# guage.net
KiCad netlist of a schematic drawn in EAGLE
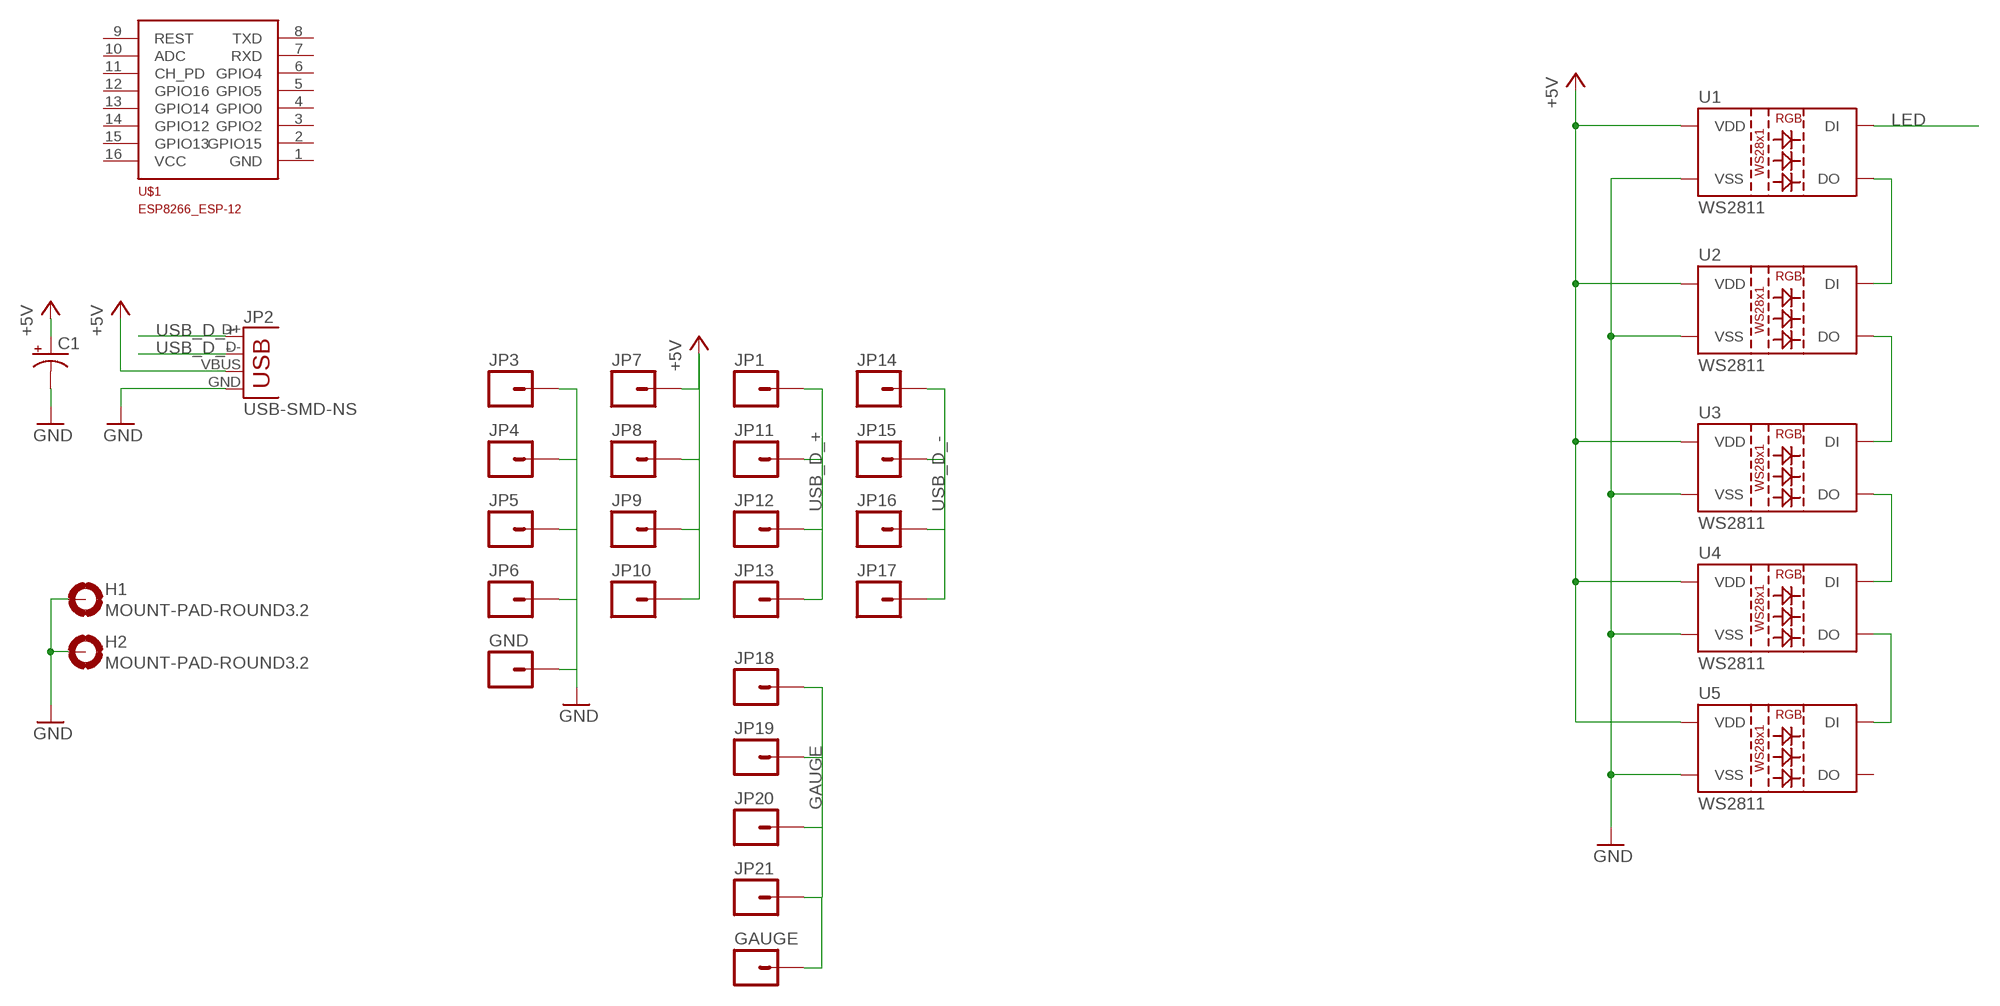
[diagram p0: schematic, sheet 1]

(export (version "E")
  (design (tool "Eeschema 10.0.6"))
  (components
    (comp (ref "C1")
      (value "100UF-25V-20%(PTH)")
      (footprint "eagle-import:CPOL-RADIAL-100UF-25V")
      (libsource (lib "eagle-import") (part "100UF-25V-20%(PTH)"))
    )
    (comp (ref "GAUGE")
      (value "M01OFFSET")
      (footprint "eagle-import:1X01_OFFSET")
      (libsource (lib "eagle-import") (part "M01OFFSET"))
    )
    (comp (ref "GND")
      (value "M01OFFSET")
      (footprint "eagle-import:1X01_OFFSET")
      (libsource (lib "eagle-import") (part "M01OFFSET"))
    )
    (comp (ref "H1")
      (value "MOUNT-PAD-ROUND3.2")
      (footprint "eagle-import:3,2-PAD")
      (libsource (lib "eagle-import") (part "MOUNT-PAD-ROUND3.2"))
    )
    (comp (ref "H2")
      (value "MOUNT-PAD-ROUND3.2")
      (footprint "eagle-import:3,2-PAD")
      (libsource (lib "eagle-import") (part "MOUNT-PAD-ROUND3.2"))
    )
    (comp (ref "JP1")
      (value "M01SMD-4.5X1.5")
      (footprint "eagle-import:PAD-1.5X4.5")
      (libsource (lib "eagle-import") (part "M01SMD-4.5X1.5"))
    )
    (comp (ref "JP2")
      (value "USB-SMD-NS")
      (footprint "eagle-import:USB-MINIB-NOSTOP")
      (libsource (lib "eagle-import") (part "USB-SMD-NS"))
    )
    (comp (ref "JP3")
      (value "M01SMD-4.5X1.5")
      (footprint "eagle-import:PAD-1.5X4.5")
      (libsource (lib "eagle-import") (part "M01SMD-4.5X1.5"))
    )
    (comp (ref "JP4")
      (value "M01SMD-4.5X1.5")
      (footprint "eagle-import:PAD-1.5X4.5")
      (libsource (lib "eagle-import") (part "M01SMD-4.5X1.5"))
    )
    (comp (ref "JP5")
      (value "M01SMD-4.5X1.5")
      (footprint "eagle-import:PAD-1.5X4.5")
      (libsource (lib "eagle-import") (part "M01SMD-4.5X1.5"))
    )
    (comp (ref "JP6")
      (value "M01SMD-4.5X1.5")
      (footprint "eagle-import:PAD-1.5X4.5")
      (libsource (lib "eagle-import") (part "M01SMD-4.5X1.5"))
    )
    (comp (ref "JP7")
      (value "M01SMD-4.5X1.5")
      (footprint "eagle-import:PAD-1.5X4.5")
      (libsource (lib "eagle-import") (part "M01SMD-4.5X1.5"))
    )
    (comp (ref "JP8")
      (value "M01SMD-4.5X1.5")
      (footprint "eagle-import:PAD-1.5X4.5")
      (libsource (lib "eagle-import") (part "M01SMD-4.5X1.5"))
    )
    (comp (ref "JP9")
      (value "M01SMD-4.5X1.5")
      (footprint "eagle-import:PAD-1.5X4.5")
      (libsource (lib "eagle-import") (part "M01SMD-4.5X1.5"))
    )
    (comp (ref "JP10")
      (value "M01SMD-4.5X1.5")
      (footprint "eagle-import:PAD-1.5X4.5")
      (libsource (lib "eagle-import") (part "M01SMD-4.5X1.5"))
    )
    (comp (ref "JP11")
      (value "M01SMD-4.5X1.5")
      (footprint "eagle-import:PAD-1.5X4.5")
      (libsource (lib "eagle-import") (part "M01SMD-4.5X1.5"))
    )
    (comp (ref "JP12")
      (value "M01SMD-4.5X1.5")
      (footprint "eagle-import:PAD-1.5X4.5")
      (libsource (lib "eagle-import") (part "M01SMD-4.5X1.5"))
    )
    (comp (ref "JP13")
      (value "M01SMD-4.5X1.5")
      (footprint "eagle-import:PAD-1.5X4.5")
      (libsource (lib "eagle-import") (part "M01SMD-4.5X1.5"))
    )
    (comp (ref "JP14")
      (value "M01SMD-4.5X1.5")
      (footprint "eagle-import:PAD-1.5X4.5")
      (libsource (lib "eagle-import") (part "M01SMD-4.5X1.5"))
    )
    (comp (ref "JP15")
      (value "M01SMD-4.5X1.5")
      (footprint "eagle-import:PAD-1.5X4.5")
      (libsource (lib "eagle-import") (part "M01SMD-4.5X1.5"))
    )
    (comp (ref "JP16")
      (value "M01SMD-4.5X1.5")
      (footprint "eagle-import:PAD-1.5X4.5")
      (libsource (lib "eagle-import") (part "M01SMD-4.5X1.5"))
    )
    (comp (ref "JP17")
      (value "M01SMD-4.5X1.5")
      (footprint "eagle-import:PAD-1.5X4.5")
      (libsource (lib "eagle-import") (part "M01SMD-4.5X1.5"))
    )
    (comp (ref "JP18")
      (value "M01SMD-4.5X1.5")
      (footprint "eagle-import:PAD-1.5X4.5")
      (libsource (lib "eagle-import") (part "M01SMD-4.5X1.5"))
    )
    (comp (ref "JP19")
      (value "M01SMD-4.5X1.5")
      (footprint "eagle-import:PAD-1.5X4.5")
      (libsource (lib "eagle-import") (part "M01SMD-4.5X1.5"))
    )
    (comp (ref "JP20")
      (value "M01SMD-4.5X1.5")
      (footprint "eagle-import:PAD-1.5X4.5")
      (libsource (lib "eagle-import") (part "M01SMD-4.5X1.5"))
    )
    (comp (ref "JP21")
      (value "M01SMD-4.5X1.5")
      (footprint "eagle-import:PAD-1.5X4.5")
      (libsource (lib "eagle-import") (part "M01SMD-4.5X1.5"))
    )
    (comp (ref "U$1")
      (value "ESP8266_ESP-12")
      (footprint "eagle-import:ESP8266-ESP12")
      (libsource (lib "eagle-import") (part "ESP8266_ESP-12"))
    )
    (comp (ref "U1")
      (value "WS2811")
      (footprint "eagle-import:LED-TRICOLOR-5050-IC")
      (libsource (lib "eagle-import") (part "LED-TRICOLOR-5050-ICWS2811"))
    )
    (comp (ref "U2")
      (value "WS2811")
      (footprint "eagle-import:LED-TRICOLOR-5050-IC")
      (libsource (lib "eagle-import") (part "LED-TRICOLOR-5050-ICWS2811"))
    )
    (comp (ref "U3")
      (value "WS2811")
      (footprint "eagle-import:LED-TRICOLOR-5050-IC")
      (libsource (lib "eagle-import") (part "LED-TRICOLOR-5050-ICWS2811"))
    )
    (comp (ref "U4")
      (value "WS2811")
      (footprint "eagle-import:LED-TRICOLOR-5050-IC")
      (libsource (lib "eagle-import") (part "LED-TRICOLOR-5050-ICWS2811"))
    )
    (comp (ref "U5")
      (value "WS2811")
      (footprint "eagle-import:LED-TRICOLOR-5050-IC")
      (libsource (lib "eagle-import") (part "LED-TRICOLOR-5050-ICWS2811"))
    )
  )
  (nets
    (net (code "1") (name "+5V") (class "Default")
      (node (ref "C1") (pin "1") (pinfunction "+_1") (pintype "passive"))
      (node (ref "JP10") (pin "P$1") (pinfunction "1_P$1") (pintype "passive"))
      (node (ref "JP2") (pin "VBUS") (pinfunction "VBUS_VBUS") (pintype "bidirectional"))
      (node (ref "JP7") (pin "P$1") (pinfunction "1_P$1") (pintype "passive"))
      (node (ref "JP8") (pin "P$1") (pinfunction "1_P$1") (pintype "passive"))
      (node (ref "JP9") (pin "P$1") (pinfunction "1_P$1") (pintype "passive"))
      (node (ref "U1") (pin "3") (pinfunction "VDD_3") (pintype "bidirectional"))
      (node (ref "U1") (pin "5") (pinfunction "VDD_5") (pintype "bidirectional"))
      (node (ref "U2") (pin "3") (pinfunction "VDD_3") (pintype "bidirectional"))
      (node (ref "U2") (pin "5") (pinfunction "VDD_5") (pintype "bidirectional"))
      (node (ref "U3") (pin "3") (pinfunction "VDD_3") (pintype "bidirectional"))
      (node (ref "U3") (pin "5") (pinfunction "VDD_5") (pintype "bidirectional"))
      (node (ref "U4") (pin "3") (pinfunction "VDD_3") (pintype "bidirectional"))
      (node (ref "U4") (pin "5") (pinfunction "VDD_5") (pintype "bidirectional"))
      (node (ref "U5") (pin "3") (pinfunction "VDD_3") (pintype "bidirectional"))
      (node (ref "U5") (pin "5") (pinfunction "VDD_5") (pintype "bidirectional"))
    )
    (net (code "2") (name "/GAUGE") (class "Default")
      (node (ref "GAUGE") (pin "1") (pinfunction "1_1") (pintype "passive"))
      (node (ref "JP18") (pin "P$1") (pinfunction "1_P$1") (pintype "passive"))
      (node (ref "JP19") (pin "P$1") (pinfunction "1_P$1") (pintype "passive"))
      (node (ref "JP20") (pin "P$1") (pinfunction "1_P$1") (pintype "passive"))
      (node (ref "JP21") (pin "P$1") (pinfunction "1_P$1") (pintype "passive"))
    )
    (net (code "3") (name "/LED") (class "Default")
      (node (ref "U1") (pin "2") (pinfunction "DI_2") (pintype "bidirectional"))
    )
    (net (code "4") (name "/USB_D_+") (class "Default")
      (node (ref "JP1") (pin "P$1") (pinfunction "1_P$1") (pintype "passive"))
      (node (ref "JP11") (pin "P$1") (pinfunction "1_P$1") (pintype "passive"))
      (node (ref "JP12") (pin "P$1") (pinfunction "1_P$1") (pintype "passive"))
      (node (ref "JP13") (pin "P$1") (pinfunction "1_P$1") (pintype "passive"))
      (node (ref "JP2") (pin "D+") (pinfunction "D+_D+") (pintype "bidirectional"))
    )
    (net (code "5") (name "/USB_D_-") (class "Default")
      (node (ref "JP14") (pin "P$1") (pinfunction "1_P$1") (pintype "passive"))
      (node (ref "JP15") (pin "P$1") (pinfunction "1_P$1") (pintype "passive"))
      (node (ref "JP16") (pin "P$1") (pinfunction "1_P$1") (pintype "passive"))
      (node (ref "JP17") (pin "P$1") (pinfunction "1_P$1") (pintype "passive"))
      (node (ref "JP2") (pin "D-") (pinfunction "D-_D-") (pintype "bidirectional"))
    )
    (net (code "6") (name "GND") (class "Default")
      (node (ref "C1") (pin "2") (pinfunction "-_2") (pintype "passive"))
      (node (ref "GND") (pin "1") (pinfunction "1_1") (pintype "passive"))
      (node (ref "H1") (pin "B3,2") (pinfunction "MOUNT_B3,2") (pintype "passive"))
      (node (ref "H2") (pin "B3,2") (pinfunction "MOUNT_B3,2") (pintype "passive"))
      (node (ref "JP2") (pin "GND") (pinfunction "GND_GND") (pintype "bidirectional"))
      (node (ref "JP3") (pin "P$1") (pinfunction "1_P$1") (pintype "passive"))
      (node (ref "JP4") (pin "P$1") (pinfunction "1_P$1") (pintype "passive"))
      (node (ref "JP5") (pin "P$1") (pinfunction "1_P$1") (pintype "passive"))
      (node (ref "JP6") (pin "P$1") (pinfunction "1_P$1") (pintype "passive"))
      (node (ref "U1") (pin "6") (pinfunction "VSS_6") (pintype "bidirectional"))
      (node (ref "U2") (pin "6") (pinfunction "VSS_6") (pintype "bidirectional"))
      (node (ref "U3") (pin "6") (pinfunction "VSS_6") (pintype "bidirectional"))
      (node (ref "U4") (pin "6") (pinfunction "VSS_6") (pintype "bidirectional"))
      (node (ref "U5") (pin "6") (pinfunction "VSS_6") (pintype "bidirectional"))
    )
    (net (code "7") (name "Net-(U1-DO)") (class "Default")
      (node (ref "U1") (pin "1") (pinfunction "DO_1") (pintype "bidirectional"))
      (node (ref "U2") (pin "2") (pinfunction "DI_2") (pintype "bidirectional"))
    )
    (net (code "8") (name "Net-(U2-DO)") (class "Default")
      (node (ref "U2") (pin "1") (pinfunction "DO_1") (pintype "bidirectional"))
      (node (ref "U3") (pin "2") (pinfunction "DI_2") (pintype "bidirectional"))
    )
    (net (code "9") (name "Net-(U3-DO)") (class "Default")
      (node (ref "U3") (pin "1") (pinfunction "DO_1") (pintype "bidirectional"))
      (node (ref "U4") (pin "2") (pinfunction "DI_2") (pintype "bidirectional"))
    )
    (net (code "10") (name "Net-(U4-DO)") (class "Default")
      (node (ref "U4") (pin "1") (pinfunction "DO_1") (pintype "bidirectional"))
      (node (ref "U5") (pin "2") (pinfunction "DI_2") (pintype "bidirectional"))
    )
    (net (code "11") (name "unconnected-(U$1-ADC-Pad10)") (class "Default")
      (node (ref "U$1") (pin "10") (pinfunction "ADC_10") (pintype "bidirectional"))
    )
    (net (code "12") (name "unconnected-(U$1-CH_PD-Pad11)") (class "Default")
      (node (ref "U$1") (pin "11") (pinfunction "CH_PD_11") (pintype "bidirectional"))
    )
    (net (code "13") (name "unconnected-(U$1-GND-Pad1)") (class "Default")
      (node (ref "U$1") (pin "1") (pinfunction "GND_1") (pintype "bidirectional"))
    )
    (net (code "14") (name "unconnected-(U$1-GPIO0-Pad4)") (class "Default")
      (node (ref "U$1") (pin "4") (pinfunction "GPIO0_4") (pintype "bidirectional"))
    )
    (net (code "15") (name "unconnected-(U$1-GPIO2-Pad3)") (class "Default")
      (node (ref "U$1") (pin "3") (pinfunction "GPIO2_3") (pintype "bidirectional"))
    )
    (net (code "16") (name "unconnected-(U$1-GPIO4-Pad6)") (class "Default")
      (node (ref "U$1") (pin "6") (pinfunction "GPIO4_6") (pintype "bidirectional"))
    )
    (net (code "17") (name "unconnected-(U$1-GPIO5-Pad5)") (class "Default")
      (node (ref "U$1") (pin "5") (pinfunction "GPIO5_5") (pintype "bidirectional"))
    )
    (net (code "18") (name "unconnected-(U$1-GPIO12-Pad14)") (class "Default")
      (node (ref "U$1") (pin "14") (pinfunction "GPIO12_14") (pintype "bidirectional"))
    )
    (net (code "19") (name "unconnected-(U$1-GPIO13-Pad15)") (class "Default")
      (node (ref "U$1") (pin "15") (pinfunction "GPIO13_15") (pintype "bidirectional"))
    )
    (net (code "20") (name "unconnected-(U$1-GPIO14-Pad13)") (class "Default")
      (node (ref "U$1") (pin "13") (pinfunction "GPIO14_13") (pintype "bidirectional"))
    )
    (net (code "21") (name "unconnected-(U$1-GPIO15-Pad2)") (class "Default")
      (node (ref "U$1") (pin "2") (pinfunction "GPIO15_2") (pintype "bidirectional"))
    )
    (net (code "22") (name "unconnected-(U$1-GPIO16-Pad12)") (class "Default")
      (node (ref "U$1") (pin "12") (pinfunction "GPIO16_12") (pintype "bidirectional"))
    )
    (net (code "23") (name "unconnected-(U$1-REST-Pad9)") (class "Default")
      (node (ref "U$1") (pin "9") (pinfunction "REST_9") (pintype "bidirectional"))
    )
    (net (code "24") (name "unconnected-(U$1-RXD-Pad7)") (class "Default")
      (node (ref "U$1") (pin "7") (pinfunction "RXD_7") (pintype "bidirectional"))
    )
    (net (code "25") (name "unconnected-(U$1-TXD-Pad8)") (class "Default")
      (node (ref "U$1") (pin "8") (pinfunction "TXD_8") (pintype "bidirectional"))
    )
    (net (code "26") (name "unconnected-(U$1-VCC-Pad16)") (class "Default")
      (node (ref "U$1") (pin "16") (pinfunction "VCC_16") (pintype "bidirectional"))
    )
    (net (code "27") (name "unconnected-(U5-DO-Pad1)") (class "Default")
      (node (ref "U5") (pin "1") (pinfunction "DO_1") (pintype "bidirectional"))
    )
  )
)
